# openSX70_EDWIN_V7-9_20191123-TSL237T.net
KiCad netlist of a schematic drawn in EAGLE
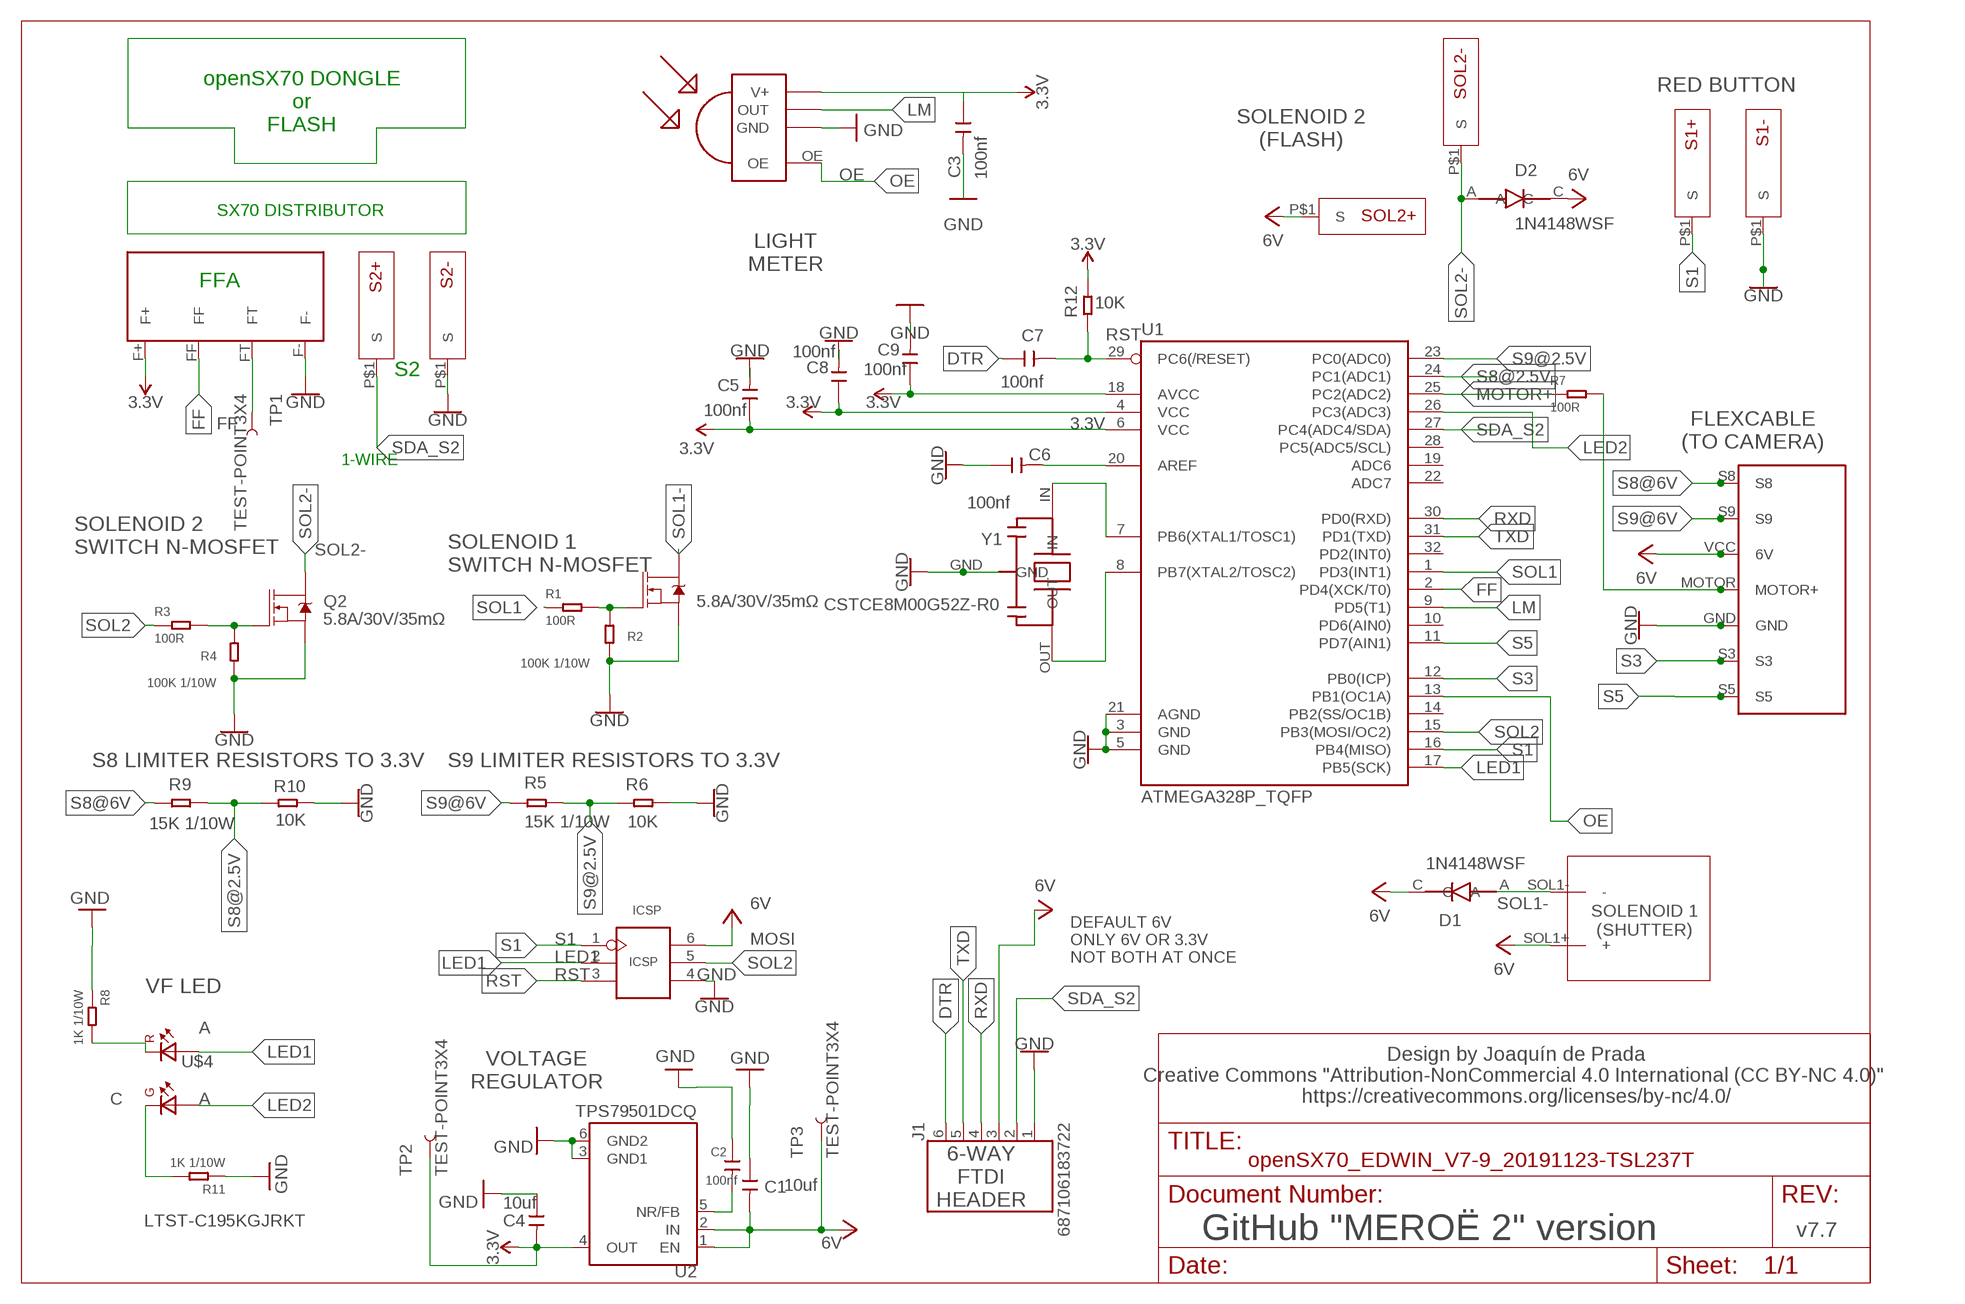
[diagram p0: schematic, sheet 1]

(export (version "E")
  (design (tool "Eeschema 10.0.6"))
  (components
    (comp (ref "C1")
      (value "10uf")
      (footprint "eagle-import:C0603")
      (fields (field (name "MPN") "CC0603KRX5R6BB106"))
      (libsource (lib "eagle-import") (part "CERAMIC-10UF-10V-10%-X5R(0603)"))
    )
    (comp (ref "C2")
      (value "100nf")
      (footprint "eagle-import:C0603")
      (fields (field (name "MPN") "CC0603KRX7R9BB104"))
      (libsource (lib "eagle-import") (part "CERAMIC-100NF-50V-10%-X7R(0603)"))
    )
    (comp (ref "C3")
      (value "100nf")
      (footprint "eagle-import:C0603")
      (fields (field (name "MPN") "CC0603KRX7R9BB104"))
      (libsource (lib "eagle-import") (part "CERAMIC-100NF-50V-10%-X7R(0603)"))
    )
    (comp (ref "C4")
      (value "10uf")
      (footprint "eagle-import:C0603")
      (fields (field (name "MPN") "CC0603KRX5R6BB106"))
      (libsource (lib "eagle-import") (part "CERAMIC-10UF-10V-10%-X5R(0603)"))
    )
    (comp (ref "C5")
      (value "100nf")
      (footprint "eagle-import:C0603")
      (fields (field (name "MPN") "CC0603KRX7R9BB104"))
      (libsource (lib "eagle-import") (part "CERAMIC-100NF-50V-10%-X7R(0603)"))
    )
    (comp (ref "C6")
      (value "100nf")
      (footprint "eagle-import:C0603")
      (fields (field (name "MPN") "CC0603KRX7R9BB104"))
      (libsource (lib "eagle-import") (part "CERAMIC-100NF-50V-10%-X7R(0603)"))
    )
    (comp (ref "C7")
      (value "100nf")
      (footprint "eagle-import:C0603")
      (fields (field (name "MPN") "CC0603KRX7R9BB104"))
      (libsource (lib "eagle-import") (part "CERAMIC-100NF-50V-10%-X7R(0603)"))
    )
    (comp (ref "C8")
      (value "100nf")
      (footprint "eagle-import:C0603")
      (fields (field (name "MPN") "CC0603KRX7R9BB104"))
      (libsource (lib "eagle-import") (part "CERAMIC-100NF-50V-10%-X7R(0603)"))
    )
    (comp (ref "C9")
      (value "100nf")
      (footprint "eagle-import:C0603")
      (fields (field (name "MPN") "CC0603KRX7R9BB104"))
      (libsource (lib "eagle-import") (part "CERAMIC-100NF-50V-10%-X7R(0603)"))
    )
    (comp (ref "D1")
      (value "1N4148WSF")
      (footprint "eagle-import:SODFL2512X100N")
      (fields (field (name "MANUFACTURER") "Fairchild Semiconductor"))
      (libsource (lib "eagle-import") (part "1N4148WS"))
    )
    (comp (ref "D2")
      (value "1N4148WSF")
      (footprint "eagle-import:SODFL2512X100N")
      (fields (field (name "MANUFACTURER") "Fairchild Semiconductor"))
      (libsource (lib "eagle-import") (part "1N4148WS"))
    )
    (comp (ref "ICSP")
      (value "ICSP")
      (footprint "eagle-import:H2X3-2.54")
      (libsource (lib "eagle-import") (part "ICSP"))
    )
    (comp (ref "J1")
      (value "687106183722")
      (footprint "eagle-import:687106183722")
      (fields (field (name "MF") "Wurth Electronics"))
      (libsource (lib "eagle-import") (part "687106183722"))
    )
    (comp (ref "Q1")
      (value "5.8A/30V/35mΩ")
      (footprint "eagle-import:SOT23-3")
      (libsource (lib "eagle-import") (part "MOSFET-NCH-AO3404A"))
    )
    (comp (ref "Q2")
      (value "5.8A/30V/35mΩ")
      (footprint "eagle-import:SOT23-3")
      (libsource (lib "eagle-import") (part "MOSFET-NCH-AO3404A"))
    )
    (comp (ref "R1")
      (value "100R")
      (footprint "eagle-import:R0603")
      (fields (field (name "MPN") "RC0603JR-07100RL"))
      (libsource (lib "eagle-import") (part "SMD-RES-100R-5%-1/10W(0603)"))
    )
    (comp (ref "R2")
      (value "100K 1/10W")
      (footprint "eagle-import:R0603")
      (fields (field (name "MPN") "RC0603JR-07100KL"))
      (libsource (lib "eagle-import") (part "SMD-RES-100K-5%-1/10W(0603)"))
    )
    (comp (ref "R3")
      (value "100R")
      (footprint "eagle-import:R0603")
      (fields (field (name "MPN") "RC0603JR-07100RL"))
      (libsource (lib "eagle-import") (part "SMD-RES-100R-5%-1/10W(0603)"))
    )
    (comp (ref "R4")
      (value "100K 1/10W")
      (footprint "eagle-import:R0603")
      (fields (field (name "MPN") "RC0603JR-07100KL"))
      (libsource (lib "eagle-import") (part "SMD-RES-100K-5%-1/10W(0603)"))
    )
    (comp (ref "R5")
      (value "15K 1/10W")
      (footprint "eagle-import:R0603")
      (fields (field (name "MPN") "RC0603FR-0715KL"))
      (libsource (lib "eagle-import") (part "SMD-RES-15K-1%-1/10W(0603)"))
    )
    (comp (ref "R6")
      (value "10K")
      (footprint "eagle-import:R0603")
      (fields (field (name "MPN") "RC0603FR-0710KL"))
      (libsource (lib "eagle-import") (part "SMD-RES-10K-1%-1/10W(0603)"))
    )
    (comp (ref "R7")
      (value "100R")
      (footprint "eagle-import:R0603")
      (fields (field (name "MPN") "RC0603JR-07100RL"))
      (libsource (lib "eagle-import") (part "SMD-RES-100R-5%-1/10W(0603)"))
    )
    (comp (ref "R8")
      (value "1K 1/10W")
      (footprint "eagle-import:R0603")
      (fields (field (name "MPN") "RC0603JR-071KL"))
      (libsource (lib "eagle-import") (part "SMD-RES-1K-5%-1/10W(0603)"))
    )
    (comp (ref "R9")
      (value "15K 1/10W")
      (footprint "eagle-import:R0603")
      (fields (field (name "MPN") "RC0603FR-0715KL"))
      (libsource (lib "eagle-import") (part "SMD-RES-15K-1%-1/10W(0603)"))
    )
    (comp (ref "R10")
      (value "10K")
      (footprint "eagle-import:R0603")
      (fields (field (name "MPN") "RC0603FR-0710KL"))
      (libsource (lib "eagle-import") (part "SMD-RES-10K-1%-1/10W(0603)"))
    )
    (comp (ref "R11")
      (value "1K 1/10W")
      (footprint "eagle-import:R0603")
      (fields (field (name "MPN") "RC0603JR-071KL"))
      (libsource (lib "eagle-import") (part "SMD-RES-1K-5%-1/10W(0603)"))
    )
    (comp (ref "R12")
      (value "10K")
      (footprint "eagle-import:R0603")
      (fields (field (name "MPN") "RC0603FR-0710KL"))
      (libsource (lib "eagle-import") (part "SMD-RES-10K-1%-1/10W(0603)"))
    )
    (comp (ref "S1+")
      (value "SX70-S-PAD-NEW")
      (footprint "eagle-import:SX70-S-PAD2")
      (libsource (lib "eagle-import") (part "SX70-S-PAD-NEW"))
    )
    (comp (ref "S1-")
      (value "SX70-S-PAD-NEW")
      (footprint "eagle-import:SX70-S-PAD2")
      (libsource (lib "eagle-import") (part "SX70-S-PAD-NEW"))
    )
    (comp (ref "S2+")
      (value "SX70-S-PAD-NEW")
      (footprint "eagle-import:SX70-S-PAD2")
      (libsource (lib "eagle-import") (part "SX70-S-PAD-NEW"))
    )
    (comp (ref "S2-")
      (value "SX70-S-PAD-NEW")
      (footprint "eagle-import:SX70-S-PAD2")
      (libsource (lib "eagle-import") (part "SX70-S-PAD-NEW"))
    )
    (comp (ref "SOL1")
      (value "SX70-SOLENOID1-2PADS")
      (footprint "eagle-import:SX70-SOLENOID1-2")
      (libsource (lib "eagle-import") (part "SX70-SOLENOID1-2PADS"))
    )
    (comp (ref "SOL2+")
      (value "SX70-S-PAD-NEW")
      (footprint "eagle-import:SX70-S-PAD2")
      (libsource (lib "eagle-import") (part "SX70-S-PAD-NEW"))
    )
    (comp (ref "SOL2-")
      (value "SX70-S-PAD-NEW")
      (footprint "eagle-import:SX70-S-PAD2")
      (libsource (lib "eagle-import") (part "SX70-S-PAD-NEW"))
    )
    (comp (ref "TP1")
      (value "TEST-POINT3X4")
      (footprint "eagle-import:PAD.03X.04")
      (libsource (lib "eagle-import") (part "TEST-POINT3X4"))
    )
    (comp (ref "TP2")
      (value "TEST-POINT3X4")
      (footprint "eagle-import:PAD.03X.04")
      (libsource (lib "eagle-import") (part "TEST-POINT3X4"))
    )
    (comp (ref "TP3")
      (value "TEST-POINT3X4")
      (footprint "eagle-import:PAD.03X.04")
      (libsource (lib "eagle-import") (part "TEST-POINT3X4"))
    )
    (comp (ref "U$1")
      (value "SX70-7-PAD")
      (footprint "eagle-import:SX70-7-PAD-PROPER")
      (libsource (lib "eagle-import") (part "SX70-7-PAD"))
    )
    (comp (ref "U$2")
      (value "FFA")
      (footprint "eagle-import:FFA-PAD-PACKAGE")
      (libsource (lib "eagle-import") (part "SX70-FFA-PAD"))
    )
    (comp (ref "U$3")
      (value "TSL237T")
      (footprint "eagle-import:TSL237T")
      (libsource (lib "eagle-import") (part "TSL237T"))
    )
    (comp (ref "U$4")
      (value "LTST-C195KGJRKT")
      (footprint "eagle-import:LTST-BILED-15X16")
      (fields (field (name "MF") "Lite-On Inc."))
      (libsource (lib "eagle-import") (part "LTST-C195KGJRKT"))
    )
    (comp (ref "U1")
      (value "ATMEGA328P_TQFP")
      (footprint "eagle-import:TQFP32-08")
      (libsource (lib "eagle-import") (part "ATMEGA328P_TQFP"))
    )
    (comp (ref "U2")
      (value "TPS79501DCQ")
      (footprint "eagle-import:SOT127P706X180-6N")
      (fields (field (name "DIGI-KEY_PART_NUMBER") "296-27102-5-ND") (field (name "MF") "Texas Instruments"))
      (libsource (lib "eagle-import") (part "TPS79501DCQ"))
    )
    (comp (ref "Y1")
      (value "CSTCE8M00G52Z-R0")
      (footprint "eagle-import:CFP95P160X100-3N")
      (fields (field (name "MF") "Murata") (field (name "MP") "CSTCE16M0V53-R0"))
      (libsource (lib "eagle-import") (part "CSTCE16M0V53-R0"))
    )
  )
  (nets
    (net (code "1") (name "3.3V") (class "Default")
      (node (ref "C3") (pin "1") (pinfunction "1_1") (pintype "passive"))
      (node (ref "C4") (pin "2") (pinfunction "2_2") (pintype "passive"))
      (node (ref "C5") (pin "1") (pinfunction "1_1") (pintype "passive"))
      (node (ref "C8") (pin "1") (pinfunction "1_1") (pintype "passive"))
      (node (ref "C9") (pin "1") (pinfunction "1_1") (pintype "passive"))
      (node (ref "R12") (pin "2") (pinfunction "2_2") (pintype "passive"))
      (node (ref "TP2") (pin "P$1") (pinfunction "1_P$1") (pintype "bidirectional"))
      (node (ref "U$2") (pin "F+") (pinfunction "F+_F+") (pintype "bidirectional"))
      (node (ref "U$3") (pin "VDD") (pinfunction "V+_VDD") (pintype "bidirectional"))
      (node (ref "U1") (pin "18") (pinfunction "AVCC_18") (pintype "bidirectional"))
      (node (ref "U1") (pin "4") (pinfunction "VCC_4") (pintype "bidirectional"))
      (node (ref "U1") (pin "6") (pinfunction "VCC_6") (pintype "bidirectional"))
      (node (ref "U2") (pin "4") (pinfunction "OUT_4") (pintype "output"))
    )
    (net (code "2") (name "6V") (class "Default")
      (node (ref "C1") (pin "2") (pinfunction "2_2") (pintype "passive"))
      (node (ref "D1") (pin "C") (pinfunction "C_C") (pintype "passive"))
      (node (ref "D2") (pin "C") (pinfunction "C_C") (pintype "passive"))
      (node (ref "ICSP") (pin "6") (pinfunction "VCC_6") (pintype "bidirectional"))
      (node (ref "J1") (pin "3") (pinfunction "4_3") (pintype "passive"))
      (node (ref "SOL1") (pin "SOL1+") (pinfunction "+_SOL1+") (pintype "bidirectional"))
      (node (ref "SOL2+") (pin "P$1") (pinfunction "S_P$1") (pintype "bidirectional"))
      (node (ref "TP3") (pin "P$1") (pinfunction "1_P$1") (pintype "bidirectional"))
      (node (ref "U$1") (pin "VCC") (pinfunction "6V_VCC") (pintype "bidirectional"))
      (node (ref "U2") (pin "1") (pinfunction "EN_1") (pintype "input"))
      (node (ref "U2") (pin "2") (pinfunction "IN_2") (pintype "input"))
    )
    (net (code "3") (name "DTR") (class "Default")
      (node (ref "C7") (pin "1") (pinfunction "1_1") (pintype "passive"))
      (node (ref "J1") (pin "6") (pinfunction "1_6") (pintype "passive"))
    )
    (net (code "4") (name "FF") (class "Default")
      (node (ref "U$2") (pin "FF") (pinfunction "FF_FF") (pintype "bidirectional"))
      (node (ref "U1") (pin "2") (pinfunction "PD4(XCK/T0)_2") (pintype "bidirectional"))
    )
    (net (code "5") (name "GND") (class "Default")
      (node (ref "C1") (pin "1") (pinfunction "1_1") (pintype "passive"))
      (node (ref "C2") (pin "1") (pinfunction "1_1") (pintype "passive"))
      (node (ref "C3") (pin "2") (pinfunction "2_2") (pintype "passive"))
      (node (ref "C4") (pin "1") (pinfunction "1_1") (pintype "passive"))
      (node (ref "C5") (pin "2") (pinfunction "2_2") (pintype "passive"))
      (node (ref "C6") (pin "1") (pinfunction "1_1") (pintype "passive"))
      (node (ref "C8") (pin "2") (pinfunction "2_2") (pintype "passive"))
      (node (ref "C9") (pin "2") (pinfunction "2_2") (pintype "passive"))
      (node (ref "ICSP") (pin "4") (pinfunction "GND_4") (pintype "bidirectional"))
      (node (ref "J1") (pin "1") (pinfunction "6_1") (pintype "passive"))
      (node (ref "Q1") (pin "2") (pinfunction "S_2") (pintype "bidirectional"))
      (node (ref "Q2") (pin "2") (pinfunction "S_2") (pintype "bidirectional"))
      (node (ref "R10") (pin "2") (pinfunction "2_2") (pintype "passive"))
      (node (ref "R11") (pin "1") (pinfunction "1_1") (pintype "passive"))
      (node (ref "R2") (pin "1") (pinfunction "1_1") (pintype "passive"))
      (node (ref "R4") (pin "1") (pinfunction "1_1") (pintype "passive"))
      (node (ref "R6") (pin "2") (pinfunction "2_2") (pintype "passive"))
      (node (ref "R8") (pin "1") (pinfunction "1_1") (pintype "passive"))
      (node (ref "S1-") (pin "P$1") (pinfunction "S_P$1") (pintype "bidirectional"))
      (node (ref "S2-") (pin "P$1") (pinfunction "S_P$1") (pintype "bidirectional"))
      (node (ref "U$1") (pin "GND") (pinfunction "GND_GND") (pintype "bidirectional"))
      (node (ref "U$2") (pin "F-") (pinfunction "F-_F-") (pintype "bidirectional"))
      (node (ref "U$3") (pin "GND") (pinfunction "GND_GND") (pintype "bidirectional"))
      (node (ref "U1") (pin "21") (pinfunction "AGND_21") (pintype "bidirectional"))
      (node (ref "U1") (pin "3") (pinfunction "GND_3") (pintype "bidirectional"))
      (node (ref "U1") (pin "5") (pinfunction "GND_5") (pintype "bidirectional"))
      (node (ref "U2") (pin "3") (pinfunction "GND1_3") (pintype "power_in"))
      (node (ref "U2") (pin "6") (pinfunction "GND2_6") (pintype "power_in"))
      (node (ref "Y1") (pin "GND") (pinfunction "GND_GND") (pintype "passive"))
    )
    (net (code "6") (name "LED1") (class "Default")
      (node (ref "ICSP") (pin "2") (pinfunction "SCK_2") (pintype "bidirectional"))
      (node (ref "U$4") (pin "P$2") (pinfunction "A2_P$2") (pintype "passive"))
      (node (ref "U1") (pin "17") (pinfunction "PB5(SCK)_17") (pintype "bidirectional"))
    )
    (net (code "7") (name "LED2") (class "Default")
      (node (ref "U$4") (pin "P$1") (pinfunction "A1_P$1") (pintype "passive"))
      (node (ref "U1") (pin "26") (pinfunction "PC3(ADC3)_26") (pintype "bidirectional"))
    )
    (net (code "8") (name "LM") (class "Default")
      (node (ref "U$3") (pin "OUT") (pinfunction "OUT_OUT") (pintype "bidirectional"))
      (node (ref "U1") (pin "9") (pinfunction "PD5(T1)_9") (pintype "bidirectional"))
    )
    (net (code "9") (name "MOTOR+") (class "Default")
      (node (ref "R7") (pin "1") (pinfunction "1_1") (pintype "passive"))
      (node (ref "U1") (pin "25") (pinfunction "PC2(ADC2)_25") (pintype "bidirectional"))
    )
    (net (code "10") (name "Net-(Q1-G)") (class "Default")
      (node (ref "Q1") (pin "1") (pinfunction "G_1") (pintype "bidirectional"))
      (node (ref "R1") (pin "2") (pinfunction "2_2") (pintype "passive"))
      (node (ref "R2") (pin "2") (pinfunction "2_2") (pintype "passive"))
    )
    (net (code "11") (name "Net-(Q2-G)") (class "Default")
      (node (ref "Q2") (pin "1") (pinfunction "G_1") (pintype "bidirectional"))
      (node (ref "R3") (pin "2") (pinfunction "2_2") (pintype "passive"))
      (node (ref "R4") (pin "2") (pinfunction "2_2") (pintype "passive"))
    )
    (net (code "12") (name "Net-(TP1-1)") (class "Default")
      (node (ref "TP1") (pin "P$1") (pinfunction "1_P$1") (pintype "bidirectional"))
      (node (ref "U$2") (pin "FT") (pinfunction "FT_FT") (pintype "bidirectional"))
    )
    (net (code "13") (name "Net-(U$1-MOTOR+)") (class "Default")
      (node (ref "R7") (pin "2") (pinfunction "2_2") (pintype "passive"))
      (node (ref "U$1") (pin "MOTOR") (pinfunction "MOTOR+_MOTOR") (pintype "bidirectional"))
    )
    (net (code "14") (name "Net-(U$4-K1)") (class "Default")
      (node (ref "R11") (pin "2") (pinfunction "2_2") (pintype "passive"))
      (node (ref "U$4") (pin "P$3") (pinfunction "K1_P$3") (pintype "passive"))
    )
    (net (code "15") (name "Net-(U$4-K2)") (class "Default")
      (node (ref "R8") (pin "2") (pinfunction "2_2") (pintype "passive"))
      (node (ref "U$4") (pin "P$4") (pinfunction "K2_P$4") (pintype "passive"))
    )
    (net (code "16") (name "Net-(U1-AREF)") (class "Default")
      (node (ref "C6") (pin "2") (pinfunction "2_2") (pintype "passive"))
      (node (ref "U1") (pin "20") (pinfunction "AREF_20") (pintype "bidirectional"))
    )
    (net (code "17") (name "Net-(U1-PB6(XTAL1{slash}TOSC1))") (class "Default")
      (node (ref "U1") (pin "7") (pinfunction "PB6(XTAL1/TOSC1)_7") (pintype "bidirectional"))
      (node (ref "Y1") (pin "IN") (pinfunction "IN_IN") (pintype "input"))
    )
    (net (code "18") (name "Net-(U1-PB7(XTAL2{slash}TOSC2))") (class "Default")
      (node (ref "U1") (pin "8") (pinfunction "PB7(XTAL2/TOSC2)_8") (pintype "bidirectional"))
      (node (ref "Y1") (pin "OUT") (pinfunction "OUT_OUT") (pintype "output"))
    )
    (net (code "19") (name "Net-(U2-NR{slash}FB)") (class "Default")
      (node (ref "C2") (pin "2") (pinfunction "2_2") (pintype "passive"))
      (node (ref "U2") (pin "5") (pinfunction "NR/FB_5") (pintype "input"))
    )
    (net (code "20") (name "OE") (class "Default")
      (node (ref "U$3") (pin "OE") (pinfunction "OE_OE") (pintype "bidirectional"))
      (node (ref "U1") (pin "13") (pinfunction "PB1(OC1A)_13") (pintype "bidirectional"))
    )
    (net (code "21") (name "RST") (class "Default")
      (node (ref "C7") (pin "2") (pinfunction "2_2") (pintype "passive"))
      (node (ref "ICSP") (pin "3") (pinfunction "RST_3") (pintype "bidirectional"))
      (node (ref "R12") (pin "1") (pinfunction "1_1") (pintype "passive"))
      (node (ref "U1") (pin "29") (pinfunction "PC6(/RESET)_29") (pintype "bidirectional"))
    )
    (net (code "22") (name "RXD") (class "Default")
      (node (ref "J1") (pin "4") (pinfunction "3_4") (pintype "passive"))
      (node (ref "U1") (pin "30") (pinfunction "PD0(RXD)_30") (pintype "bidirectional"))
    )
    (net (code "23") (name "S1") (class "Default")
      (node (ref "ICSP") (pin "1") (pinfunction "MISO_1") (pintype "bidirectional"))
      (node (ref "S1+") (pin "P$1") (pinfunction "S_P$1") (pintype "bidirectional"))
      (node (ref "U1") (pin "16") (pinfunction "PB4(MISO)_16") (pintype "bidirectional"))
    )
    (net (code "24") (name "S3") (class "Default")
      (node (ref "U$1") (pin "S3") (pinfunction "S3_S3") (pintype "bidirectional"))
      (node (ref "U1") (pin "12") (pinfunction "PB0(ICP)_12") (pintype "bidirectional"))
    )
    (net (code "25") (name "S5") (class "Default")
      (node (ref "U$1") (pin "S5") (pinfunction "S5_S5") (pintype "bidirectional"))
      (node (ref "U1") (pin "11") (pinfunction "PD7(AIN1)_11") (pintype "bidirectional"))
    )
    (net (code "26") (name "S8@2.5V") (class "Default")
      (node (ref "R10") (pin "1") (pinfunction "1_1") (pintype "passive"))
      (node (ref "R9") (pin "2") (pinfunction "2_2") (pintype "passive"))
      (node (ref "U1") (pin "24") (pinfunction "PC1(ADC1)_24") (pintype "bidirectional"))
    )
    (net (code "27") (name "S8@6V") (class "Default")
      (node (ref "R9") (pin "1") (pinfunction "1_1") (pintype "passive"))
      (node (ref "U$1") (pin "S8") (pinfunction "S8_S8") (pintype "bidirectional"))
    )
    (net (code "28") (name "S9@2.5V") (class "Default")
      (node (ref "R5") (pin "2") (pinfunction "2_2") (pintype "passive"))
      (node (ref "R6") (pin "1") (pinfunction "1_1") (pintype "passive"))
      (node (ref "U1") (pin "23") (pinfunction "PC0(ADC0)_23") (pintype "bidirectional"))
    )
    (net (code "29") (name "S9@6V") (class "Default")
      (node (ref "R5") (pin "1") (pinfunction "1_1") (pintype "passive"))
      (node (ref "U$1") (pin "S9") (pinfunction "S9_S9") (pintype "bidirectional"))
    )
    (net (code "30") (name "SDA_S2") (class "Default")
      (node (ref "J1") (pin "2") (pinfunction "5_2") (pintype "passive"))
      (node (ref "S2+") (pin "P$1") (pinfunction "S_P$1") (pintype "bidirectional"))
      (node (ref "U1") (pin "27") (pinfunction "PC4(ADC4/SDA)_27") (pintype "bidirectional"))
    )
    (net (code "31") (name "SOL1") (class "Default")
      (node (ref "R1") (pin "1") (pinfunction "1_1") (pintype "passive"))
      (node (ref "U1") (pin "1") (pinfunction "PD3(INT1)_1") (pintype "bidirectional"))
    )
    (net (code "32") (name "SOL1-") (class "Default")
      (node (ref "D1") (pin "A") (pinfunction "A_A") (pintype "passive"))
      (node (ref "Q1") (pin "3") (pinfunction "D_3") (pintype "bidirectional"))
      (node (ref "SOL1") (pin "SOL1-") (pinfunction "-_SOL1-") (pintype "bidirectional"))
    )
    (net (code "33") (name "SOL2") (class "Default")
      (node (ref "ICSP") (pin "5") (pinfunction "MOSI_5") (pintype "bidirectional"))
      (node (ref "R3") (pin "1") (pinfunction "1_1") (pintype "passive"))
      (node (ref "U1") (pin "15") (pinfunction "PB3(MOSI/OC2)_15") (pintype "bidirectional"))
    )
    (net (code "34") (name "SOL2-") (class "Default")
      (node (ref "D2") (pin "A") (pinfunction "A_A") (pintype "passive"))
      (node (ref "Q2") (pin "3") (pinfunction "D_3") (pintype "bidirectional"))
      (node (ref "SOL2-") (pin "P$1") (pinfunction "S_P$1") (pintype "bidirectional"))
    )
    (net (code "35") (name "TXD") (class "Default")
      (node (ref "J1") (pin "5") (pinfunction "2_5") (pintype "passive"))
      (node (ref "U1") (pin "31") (pinfunction "PD1(TXD)_31") (pintype "bidirectional"))
    )
    (net (code "36") (name "unconnected-(U1-ADC6-Pad19)") (class "Default")
      (node (ref "U1") (pin "19") (pinfunction "ADC6_19") (pintype "bidirectional"))
    )
    (net (code "37") (name "unconnected-(U1-ADC7-Pad22)") (class "Default")
      (node (ref "U1") (pin "22") (pinfunction "ADC7_22") (pintype "bidirectional"))
    )
    (net (code "38") (name "unconnected-(U1-PB2(SS{slash}OC1B)-Pad14)") (class "Default")
      (node (ref "U1") (pin "14") (pinfunction "PB2(SS/OC1B)_14") (pintype "bidirectional"))
    )
    (net (code "39") (name "unconnected-(U1-PC5(ADC5{slash}SCL)-Pad28)") (class "Default")
      (node (ref "U1") (pin "28") (pinfunction "PC5(ADC5/SCL)_28") (pintype "bidirectional"))
    )
    (net (code "40") (name "unconnected-(U1-PD2(INT0)-Pad32)") (class "Default")
      (node (ref "U1") (pin "32") (pinfunction "PD2(INT0)_32") (pintype "bidirectional"))
    )
    (net (code "41") (name "unconnected-(U1-PD6(AIN0)-Pad10)") (class "Default")
      (node (ref "U1") (pin "10") (pinfunction "PD6(AIN0)_10") (pintype "bidirectional"))
    )
  )
)
